# XTIO.net
KiCad netlist of a schematic drawn in Altium Designer
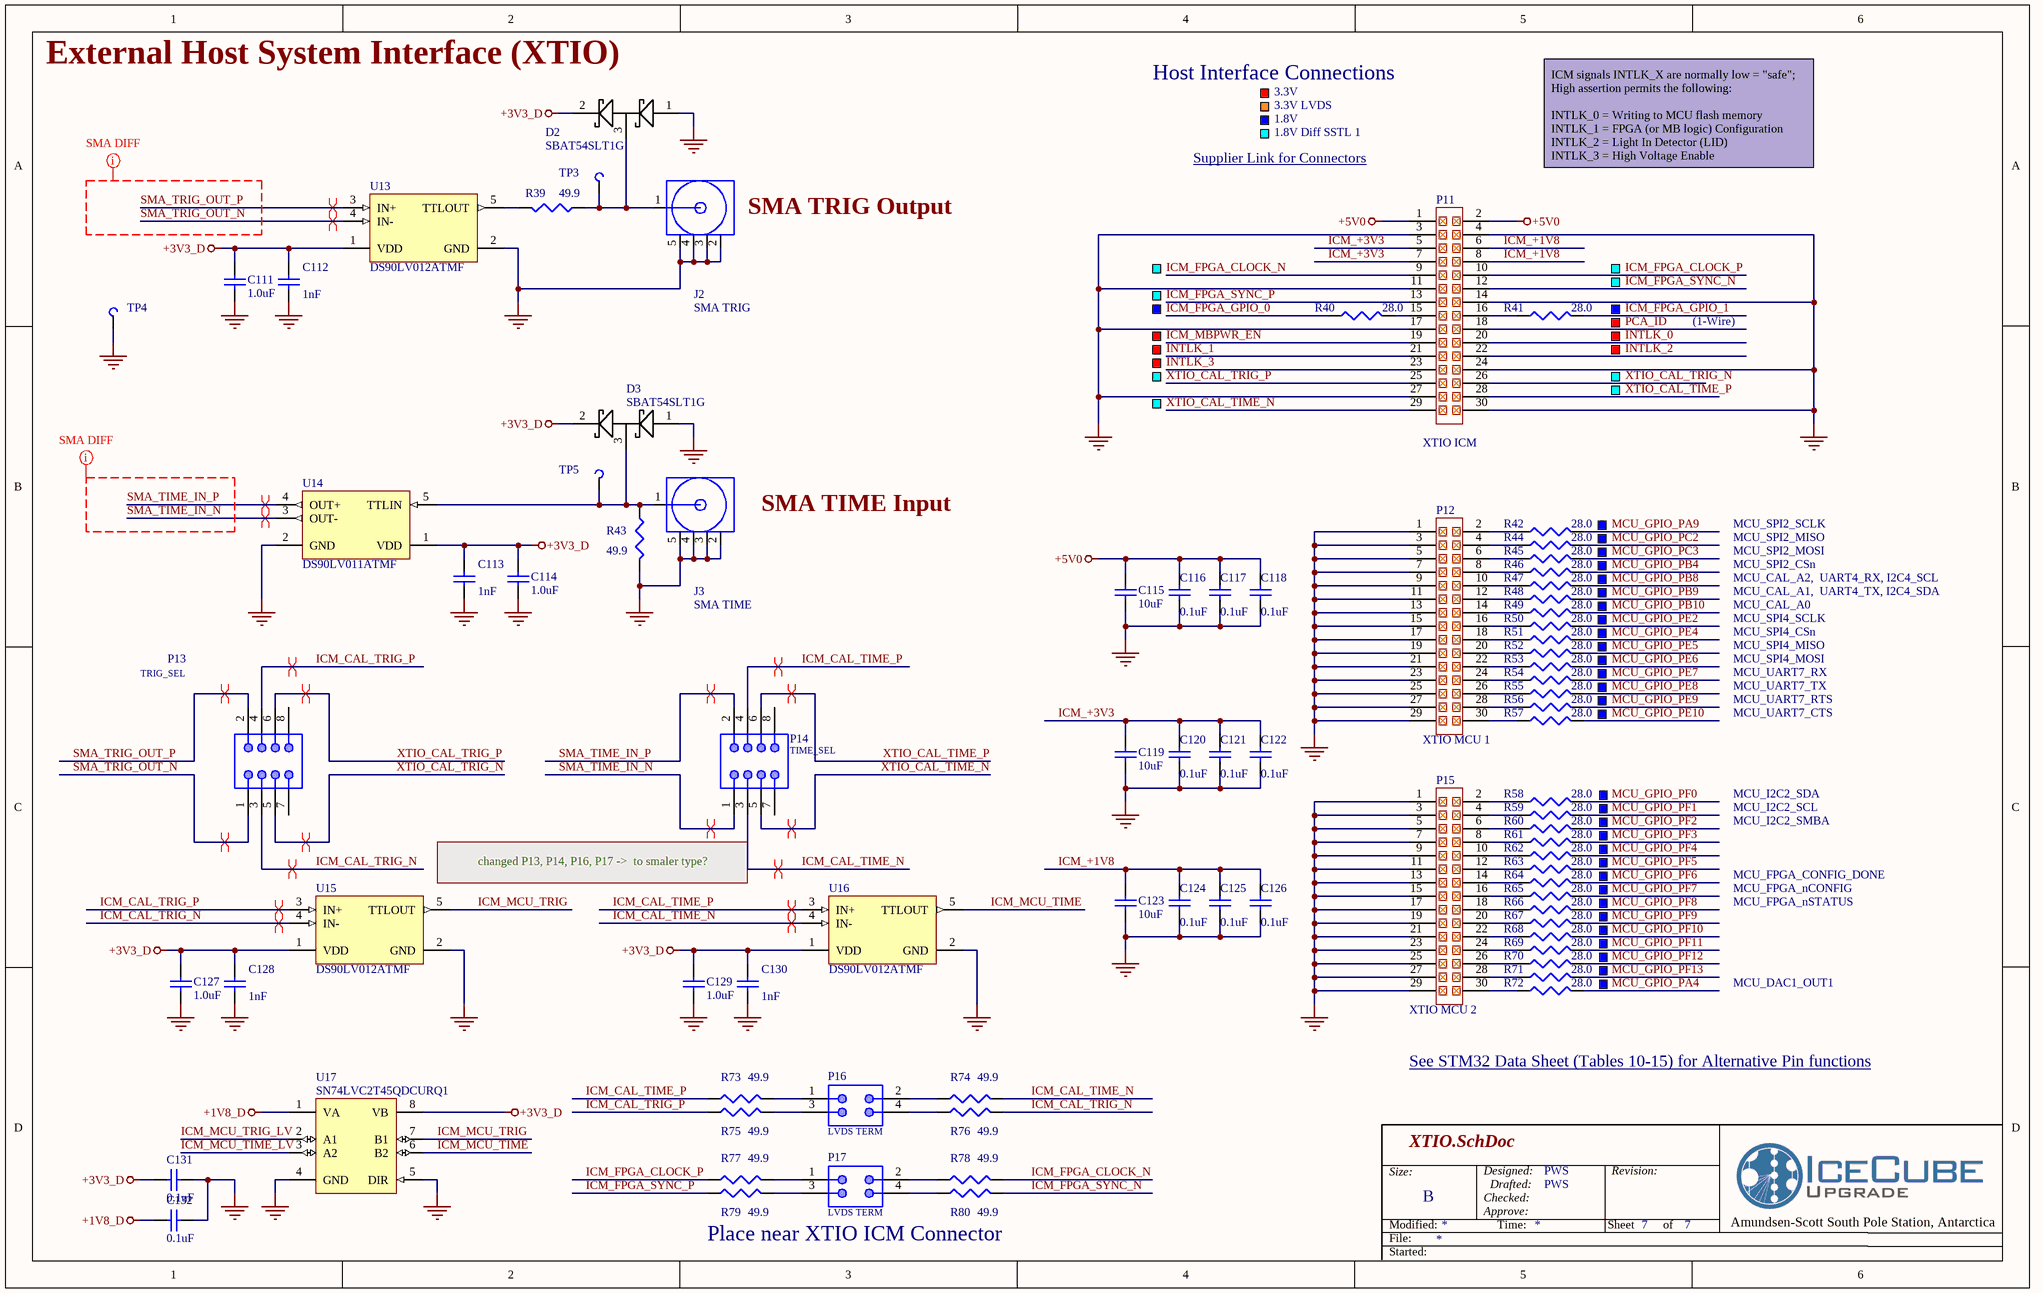
[diagram p0: XTIO.SchDoc]

(export (version "E")
  (design (tool "Eeschema 10.0.6"))
  (components
    (comp (ref "C111")
      (value "1.0uF_603_25V")
      (footprint "CAPC_0603")
      (description "1µF ±10% 25V Ceramic Capacitor X7R 0603 (1608 Metric)")
      (fields
        (field (name "MANUFACTURER") "Murata")
        (field (name "MANUFACTURER PART NUMBER") "GCJ188R71E105KA01D")
        (field (name "CAPACITANCE") "1.0uF")
      )
      (libsource (lib "Custom1") (part "CapC_1.0uF_603_25V"))
    )
    (comp (ref "C112")
      (value "1000pF_603_50V")
      (footprint "CAPC_0603")
      (description "Capacitor")
      (fields
        (field (name "MANUFACTURER") "Knowles Syfer")
        (field (name "MANUFACTURER PART NUMBER") "0603Y0500102KXT")
        (field (name "CAPACITANCE") "1nF")
      )
      (libsource (lib "Custom1") (part "CapC_1000pF_603_50V"))
    )
    (comp (ref "C113")
      (value "1000pF_603_50V")
      (footprint "CAPC_0603")
      (description "Capacitor")
      (fields
        (field (name "MANUFACTURER") "Knowles Syfer")
        (field (name "MANUFACTURER PART NUMBER") "0603Y0500102KXT")
        (field (name "CAPACITANCE") "1nF")
      )
      (libsource (lib "Custom1") (part "CapC_1000pF_603_50V"))
    )
    (comp (ref "C114")
      (value "1.0uF_603_25V")
      (footprint "CAPC_0603")
      (description "1µF ±10% 25V Ceramic Capacitor X7R 0603 (1608 Metric)")
      (fields
        (field (name "MANUFACTURER") "Murata")
        (field (name "MANUFACTURER PART NUMBER") "GCJ188R71E105KA01D")
        (field (name "CAPACITANCE") "1.0uF")
      )
      (libsource (lib "Custom1") (part "CapC_1.0uF_603_25V"))
    )
    (comp (ref "C115")
      (value "10uF_805_10V")
      (footprint "CAPC_0805")
      (description "Capacitor")
      (fields
        (field (name "MANUFACTURER") "Murata")
        (field (name "MANUFACTURER PART NUMBER") "GCJ21BR71A106KE01L")
        (field (name "CAPACITANCE") "10uF")
      )
      (libsource (lib "Custom1") (part "CapC_10uF_805_10V"))
    )
    (comp (ref "C116")
      (value "0.1uF_603_50V")
      (footprint "CAPC_0603")
      (description "0.1µF ±10% 50V Ceramic Capacitor X7R 0603 (1608 Metric)")
      (fields
        (field (name "MANUFACTURER") "Murata")
        (field (name "MANUFACTURER PART NUMBER") "GCJ188R71H104KA12D")
        (field (name "CAPACITANCE") "0.1uF")
      )
      (libsource (lib "Custom1") (part "CapC_0.1uF_603_50V_GCJ"))
    )
    (comp (ref "C117")
      (value "0.1uF_603_50V")
      (footprint "CAPC_0603")
      (description "0.1µF ±10% 50V Ceramic Capacitor X7R 0603 (1608 Metric)")
      (fields
        (field (name "MANUFACTURER") "Murata")
        (field (name "MANUFACTURER PART NUMBER") "GCJ188R71H104KA12D")
        (field (name "CAPACITANCE") "0.1uF")
      )
      (libsource (lib "Custom1") (part "CapC_0.1uF_603_50V_GCJ"))
    )
    (comp (ref "C118")
      (value "0.1uF_603_50V")
      (footprint "CAPC_0603")
      (description "0.1µF ±10% 50V Ceramic Capacitor X7R 0603 (1608 Metric)")
      (fields
        (field (name "MANUFACTURER") "Murata")
        (field (name "MANUFACTURER PART NUMBER") "GCJ188R71H104KA12D")
        (field (name "CAPACITANCE") "0.1uF")
      )
      (libsource (lib "Custom1") (part "CapC_0.1uF_603_50V_GCJ"))
    )
    (comp (ref "C119")
      (value "10uF_805_10V")
      (footprint "CAPC_0805")
      (description "Capacitor")
      (fields
        (field (name "MANUFACTURER") "Murata")
        (field (name "MANUFACTURER PART NUMBER") "GCJ21BR71A106KE01L")
        (field (name "CAPACITANCE") "10uF")
      )
      (libsource (lib "Custom1") (part "CapC_10uF_805_10V"))
    )
    (comp (ref "C120")
      (value "0.1uF_603_50V")
      (footprint "CAPC_0603")
      (description "0.1µF ±10% 50V Ceramic Capacitor X7R 0603 (1608 Metric)")
      (fields
        (field (name "MANUFACTURER") "Murata")
        (field (name "MANUFACTURER PART NUMBER") "GCJ188R71H104KA12D")
        (field (name "CAPACITANCE") "0.1uF")
      )
      (libsource (lib "Custom1") (part "CapC_0.1uF_603_50V_GCJ"))
    )
    (comp (ref "C121")
      (value "0.1uF_603_50V")
      (footprint "CAPC_0603")
      (description "0.1µF ±10% 50V Ceramic Capacitor X7R 0603 (1608 Metric)")
      (fields
        (field (name "MANUFACTURER") "Murata")
        (field (name "MANUFACTURER PART NUMBER") "GCJ188R71H104KA12D")
        (field (name "CAPACITANCE") "0.1uF")
      )
      (libsource (lib "Custom1") (part "CapC_0.1uF_603_50V_GCJ"))
    )
    (comp (ref "C122")
      (value "0.1uF_603_50V")
      (footprint "CAPC_0603")
      (description "0.1µF ±10% 50V Ceramic Capacitor X7R 0603 (1608 Metric)")
      (fields
        (field (name "MANUFACTURER") "Murata")
        (field (name "MANUFACTURER PART NUMBER") "GCJ188R71H104KA12D")
        (field (name "CAPACITANCE") "0.1uF")
      )
      (libsource (lib "Custom1") (part "CapC_0.1uF_603_50V_GCJ"))
    )
    (comp (ref "C123")
      (value "10uF_805_10V")
      (footprint "CAPC_0805")
      (description "Capacitor")
      (fields
        (field (name "MANUFACTURER") "Murata")
        (field (name "MANUFACTURER PART NUMBER") "GCJ21BR71A106KE01L")
        (field (name "CAPACITANCE") "10uF")
      )
      (libsource (lib "Custom1") (part "CapC_10uF_805_10V"))
    )
    (comp (ref "C124")
      (value "0.1uF_603_50V")
      (footprint "CAPC_0603")
      (description "0.1µF ±10% 50V Ceramic Capacitor X7R 0603 (1608 Metric)")
      (fields
        (field (name "MANUFACTURER") "Murata")
        (field (name "MANUFACTURER PART NUMBER") "GCJ188R71H104KA12D")
        (field (name "CAPACITANCE") "0.1uF")
      )
      (libsource (lib "Custom1") (part "CapC_0.1uF_603_50V_GCJ"))
    )
    (comp (ref "C125")
      (value "0.1uF_603_50V")
      (footprint "CAPC_0603")
      (description "0.1µF ±10% 50V Ceramic Capacitor X7R 0603 (1608 Metric)")
      (fields
        (field (name "MANUFACTURER") "Murata")
        (field (name "MANUFACTURER PART NUMBER") "GCJ188R71H104KA12D")
        (field (name "CAPACITANCE") "0.1uF")
      )
      (libsource (lib "Custom1") (part "CapC_0.1uF_603_50V_GCJ"))
    )
    (comp (ref "C126")
      (value "0.1uF_603_50V")
      (footprint "CAPC_0603")
      (description "0.1µF ±10% 50V Ceramic Capacitor X7R 0603 (1608 Metric)")
      (fields
        (field (name "MANUFACTURER") "Murata")
        (field (name "MANUFACTURER PART NUMBER") "GCJ188R71H104KA12D")
        (field (name "CAPACITANCE") "0.1uF")
      )
      (libsource (lib "Custom1") (part "CapC_0.1uF_603_50V_GCJ"))
    )
    (comp (ref "C127")
      (value "1.0uF_603_25V")
      (footprint "CAPC_0603")
      (description "1µF ±10% 25V Ceramic Capacitor X7R 0603 (1608 Metric)")
      (fields
        (field (name "MANUFACTURER") "Murata")
        (field (name "MANUFACTURER PART NUMBER") "GCJ188R71E105KA01D")
        (field (name "CAPACITANCE") "1.0uF")
      )
      (libsource (lib "Custom1") (part "CapC_1.0uF_603_25V"))
    )
    (comp (ref "C128")
      (value "1000pF_603_50V")
      (footprint "CAPC_0603")
      (description "Capacitor")
      (fields
        (field (name "MANUFACTURER") "Knowles Syfer")
        (field (name "MANUFACTURER PART NUMBER") "0603Y0500102KXT")
        (field (name "CAPACITANCE") "1nF")
      )
      (libsource (lib "Custom1") (part "CapC_1000pF_603_50V"))
    )
    (comp (ref "C129")
      (value "1.0uF_603_25V")
      (footprint "CAPC_0603")
      (description "1µF ±10% 25V Ceramic Capacitor X7R 0603 (1608 Metric)")
      (fields
        (field (name "MANUFACTURER") "Murata")
        (field (name "MANUFACTURER PART NUMBER") "GCJ188R71E105KA01D")
        (field (name "CAPACITANCE") "1.0uF")
      )
      (libsource (lib "Custom1") (part "CapC_1.0uF_603_25V"))
    )
    (comp (ref "C130")
      (value "1000pF_603_50V")
      (footprint "CAPC_0603")
      (description "Capacitor")
      (fields
        (field (name "MANUFACTURER") "Knowles Syfer")
        (field (name "MANUFACTURER PART NUMBER") "0603Y0500102KXT")
        (field (name "CAPACITANCE") "1nF")
      )
      (libsource (lib "Custom1") (part "CapC_1000pF_603_50V"))
    )
    (comp (ref "C131")
      (value "0.1uF_603_50V")
      (footprint "CAPC_0603")
      (description "0.1µF ±10% 50V Ceramic Capacitor X7R 0603 (1608 Metric)")
      (fields
        (field (name "MANUFACTURER") "TDK")
        (field (name "MANUFACTURER PART NUMBER") "CGJ3E2X7R1H104K080AA")
        (field (name "CAPACITANCE") "0.1uF")
      )
      (libsource (lib "Custom1") (part "CapC_0.1uF_603_50V"))
    )
    (comp (ref "C132")
      (value "0.1uF_603_50V")
      (footprint "CAPC_0603")
      (description "0.1µF ±10% 50V Ceramic Capacitor X7R 0603 (1608 Metric)")
      (fields
        (field (name "MANUFACTURER") "TDK")
        (field (name "MANUFACTURER PART NUMBER") "CGJ3E2X7R1H104K080AA")
        (field (name "CAPACITANCE") "0.1uF")
      )
      (libsource (lib "Custom1") (part "CapC_0.1uF_603_50V"))
    )
    (comp (ref "D2")
      (value "SBAT54SLT1G")
      (footprint "SOT-23")
      (description "DIODE ARRAY SCHOTTKY 30V SOT23-3")
      (fields (field (name "MANUFACTURER") "ON Semiconductor"))
      (libsource (lib "Custom1") (part "Diode ESD Pair"))
    )
    (comp (ref "D3")
      (value "SBAT54SLT1G")
      (footprint "SOT-23")
      (description "DIODE ARRAY SCHOTTKY 30V SOT23-3")
      (fields (field (name "MANUFACTURER") "ON Semiconductor"))
      (libsource (lib "Custom1") (part "Diode ESD Pair"))
    )
    (comp (ref "J2")
      (value "SMA TRIG")
      (footprint "SMA Vertical 200LS")
      (description "SMA Vertical, 0.200\"LS")
      (fields
        (field (name "MANUFACTURER") "Emerson Network Power Connectivity Johnson")
        (field (name "MANUFACTURER PART NUMBER") "142-0701-231")
      )
      (libsource (lib "Custom1") (part "SMA-Vertical"))
    )
    (comp (ref "J3")
      (value "SMA TIME")
      (footprint "SMA Vertical 200LS")
      (description "SMA Vertical, 0.200\"LS")
      (fields
        (field (name "MANUFACTURER") "Emerson Network Power Connectivity Johnson")
        (field (name "MANUFACTURER PART NUMBER") "142-0701-231")
      )
      (libsource (lib "Custom1") (part "SMA-Vertical"))
    )
    (comp (ref "P11")
      (value "XTIO ICM")
      (footprint "45230-220230")
      (description "CONN HEADER SMD 30POS 1.27MM")
      (fields (field (name "MANUFACTURER") "3M") (field (name "MANUFACTURER PART NUMBER") "45230-220230"))
      (libsource (lib "Custom1") (part "Header Male 3M-452 15x2"))
    )
    (comp (ref "P12")
      (value "XTIO MCU 1")
      (footprint "45230-220230")
      (description "CONN HEADER SMD 30POS 1.27MM")
      (fields (field (name "MANUFACTURER") "3M") (field (name "MANUFACTURER PART NUMBER") "45230-220230"))
      (libsource (lib "Custom1") (part "Header Male 3M-452 15x2"))
    )
    (comp (ref "P13")
      (value "TRIG_SEL")
      (footprint "62100821021")
      (description "WR-PHD Pin Header, SMT, pitch 1.27mm, Dual Row, Vertical, 8pin")
      (fields (field (name "PART NUMBER") "62100821021") (field (name "PUBLISHER") "Wurth Elektronik"))
      (libsource (lib "WR-PHD") (part "62100821021"))
    )
    (comp (ref "P14")
      (value "TIME_SEL")
      (footprint "62100821021")
      (description "WR-PHD Pin Header, SMT, pitch 1.27mm, Dual Row, Vertical, 8pin")
      (fields (field (name "PART NUMBER") "62100821021") (field (name "PUBLISHER") "Wurth Elektronik"))
      (libsource (lib "WR-PHD") (part "62100821021"))
    )
    (comp (ref "P15")
      (value "XTIO MCU 2")
      (footprint "45230-220230")
      (description "CONN HEADER SMD 30POS 1.27MM")
      (fields (field (name "MANUFACTURER") "3M") (field (name "MANUFACTURER PART NUMBER") "45230-220230"))
      (libsource (lib "Custom1") (part "Header Male 3M-452 15x2"))
    )
    (comp (ref "P16")
      (value "LVDS TERM")
      (footprint "62100421021")
      (description "WR-PHD Pin Header, SMT, pitch 1.27mm, Dual Row, Vertical, 4pin")
      (fields (field (name "PART NUMBER") "62100421021") (field (name "PUBLISHER") "Wurth Elektronik"))
      (libsource (lib "WR-PHD") (part "62100421021"))
    )
    (comp (ref "P17")
      (value "LVDS TERM")
      (footprint "62100421021")
      (description "WR-PHD Pin Header, SMT, pitch 1.27mm, Dual Row, Vertical, 4pin")
      (fields (field (name "PART NUMBER") "62100421021") (field (name "PUBLISHER") "Wurth Elektronik"))
      (libsource (lib "WR-PHD") (part "62100421021"))
    )
    (comp (ref "R39")
      (value "R_49.9_1206_1%")
      (footprint "RES_1206")
      (description "RES 50 OHM 1/2W 1% 1206 SMD")
      (fields
        (field (name "MANUFACTURER") "Panasonic")
        (field (name "MANUFACTURER PART NUMBER") "ERJ8ENF49R9V")
        (field (name "RESISTANCE") "49.9")
      )
      (libsource (lib "Custom1") (part "R_49.9_1206_1%"))
    )
    (comp (ref "R40")
      (value "R_28.0_603_1%")
      (footprint "RES_0603")
      (description "RES 28.0 OHM 1/10W 1% 0603 SMD")
      (fields
        (field (name "MANUFACTURER") "Panasonic")
        (field (name "MANUFACTURER PART NUMBER") "ERJ3EKF28R0V")
        (field (name "RESISTANCE") "28.0")
      )
      (libsource (lib "Custom1") (part "R_28.0_603_1%"))
    )
    (comp (ref "R41")
      (value "R_28.0_603_1%")
      (footprint "RES_0603")
      (description "RES 28.0 OHM 1/10W 1% 0603 SMD")
      (fields
        (field (name "MANUFACTURER") "Panasonic")
        (field (name "MANUFACTURER PART NUMBER") "ERJ3EKF28R0V")
        (field (name "RESISTANCE") "28.0")
      )
      (libsource (lib "Custom1") (part "R_28.0_603_1%"))
    )
    (comp (ref "R42")
      (value "R_28.0_603_1%")
      (footprint "RES_0603")
      (description "RES 28.0 OHM 1/10W 1% 0603 SMD")
      (fields
        (field (name "MANUFACTURER") "Panasonic")
        (field (name "MANUFACTURER PART NUMBER") "ERJ3EKF28R0V")
        (field (name "RESISTANCE") "28.0")
      )
      (libsource (lib "Custom1") (part "R_28.0_603_1%"))
    )
    (comp (ref "R43")
      (value "R_49.9_1206_1%")
      (footprint "RES_1206")
      (description "RES 50 OHM 1/2W 1% 1206 SMD")
      (fields
        (field (name "MANUFACTURER") "Panasonic")
        (field (name "MANUFACTURER PART NUMBER") "ERJ8ENF49R9V")
        (field (name "RESISTANCE") "49.9")
      )
      (libsource (lib "Custom1") (part "R_49.9_1206_1%"))
    )
    (comp (ref "R44")
      (value "R_28.0_603_1%")
      (footprint "RES_0603")
      (description "RES 28.0 OHM 1/10W 1% 0603 SMD")
      (fields
        (field (name "MANUFACTURER") "Panasonic")
        (field (name "MANUFACTURER PART NUMBER") "ERJ3EKF28R0V")
        (field (name "RESISTANCE") "28.0")
      )
      (libsource (lib "Custom1") (part "R_28.0_603_1%"))
    )
    (comp (ref "R45")
      (value "R_28.0_603_1%")
      (footprint "RES_0603")
      (description "RES 28.0 OHM 1/10W 1% 0603 SMD")
      (fields
        (field (name "MANUFACTURER") "Panasonic")
        (field (name "MANUFACTURER PART NUMBER") "ERJ3EKF28R0V")
        (field (name "RESISTANCE") "28.0")
      )
      (libsource (lib "Custom1") (part "R_28.0_603_1%"))
    )
    (comp (ref "R46")
      (value "R_28.0_603_1%")
      (footprint "RES_0603")
      (description "RES 28.0 OHM 1/10W 1% 0603 SMD")
      (fields
        (field (name "MANUFACTURER") "Panasonic")
        (field (name "MANUFACTURER PART NUMBER") "ERJ3EKF28R0V")
        (field (name "RESISTANCE") "28.0")
      )
      (libsource (lib "Custom1") (part "R_28.0_603_1%"))
    )
    (comp (ref "R47")
      (value "R_28.0_603_1%")
      (footprint "RES_0603")
      (description "RES 28.0 OHM 1/10W 1% 0603 SMD")
      (fields
        (field (name "MANUFACTURER") "Panasonic")
        (field (name "MANUFACTURER PART NUMBER") "ERJ3EKF28R0V")
        (field (name "RESISTANCE") "28.0")
      )
      (libsource (lib "Custom1") (part "R_28.0_603_1%"))
    )
    (comp (ref "R48")
      (value "R_28.0_603_1%")
      (footprint "RES_0603")
      (description "RES 28.0 OHM 1/10W 1% 0603 SMD")
      (fields
        (field (name "MANUFACTURER") "Panasonic")
        (field (name "MANUFACTURER PART NUMBER") "ERJ3EKF28R0V")
        (field (name "RESISTANCE") "28.0")
      )
      (libsource (lib "Custom1") (part "R_28.0_603_1%"))
    )
    (comp (ref "R49")
      (value "R_28.0_603_1%")
      (footprint "RES_0603")
      (description "RES 28.0 OHM 1/10W 1% 0603 SMD")
      (fields
        (field (name "MANUFACTURER") "Panasonic")
        (field (name "MANUFACTURER PART NUMBER") "ERJ3EKF28R0V")
        (field (name "RESISTANCE") "28.0")
      )
      (libsource (lib "Custom1") (part "R_28.0_603_1%"))
    )
    (comp (ref "R50")
      (value "R_28.0_603_1%")
      (footprint "RES_0603")
      (description "RES 28.0 OHM 1/10W 1% 0603 SMD")
      (fields
        (field (name "MANUFACTURER") "Panasonic")
        (field (name "MANUFACTURER PART NUMBER") "ERJ3EKF28R0V")
        (field (name "RESISTANCE") "28.0")
      )
      (libsource (lib "Custom1") (part "R_28.0_603_1%"))
    )
    (comp (ref "R51")
      (value "R_28.0_603_1%")
      (footprint "RES_0603")
      (description "RES 28.0 OHM 1/10W 1% 0603 SMD")
      (fields
        (field (name "MANUFACTURER") "Panasonic")
        (field (name "MANUFACTURER PART NUMBER") "ERJ3EKF28R0V")
        (field (name "RESISTANCE") "28.0")
      )
      (libsource (lib "Custom1") (part "R_28.0_603_1%"))
    )
    (comp (ref "R52")
      (value "R_28.0_603_1%")
      (footprint "RES_0603")
      (description "RES 28.0 OHM 1/10W 1% 0603 SMD")
      (fields
        (field (name "MANUFACTURER") "Panasonic")
        (field (name "MANUFACTURER PART NUMBER") "ERJ3EKF28R0V")
        (field (name "RESISTANCE") "28.0")
      )
      (libsource (lib "Custom1") (part "R_28.0_603_1%"))
    )
    (comp (ref "R53")
      (value "R_28.0_603_1%")
      (footprint "RES_0603")
      (description "RES 28.0 OHM 1/10W 1% 0603 SMD")
      (fields
        (field (name "MANUFACTURER") "Panasonic")
        (field (name "MANUFACTURER PART NUMBER") "ERJ3EKF28R0V")
        (field (name "RESISTANCE") "28.0")
      )
      (libsource (lib "Custom1") (part "R_28.0_603_1%"))
    )
    (comp (ref "R54")
      (value "R_28.0_603_1%")
      (footprint "RES_0603")
      (description "RES 28.0 OHM 1/10W 1% 0603 SMD")
      (fields
        (field (name "MANUFACTURER") "Panasonic")
        (field (name "MANUFACTURER PART NUMBER") "ERJ3EKF28R0V")
        (field (name "RESISTANCE") "28.0")
      )
      (libsource (lib "Custom1") (part "R_28.0_603_1%"))
    )
    (comp (ref "R55")
      (value "R_28.0_603_1%")
      (footprint "RES_0603")
      (description "RES 28.0 OHM 1/10W 1% 0603 SMD")
      (fields
        (field (name "MANUFACTURER") "Panasonic")
        (field (name "MANUFACTURER PART NUMBER") "ERJ3EKF28R0V")
        (field (name "RESISTANCE") "28.0")
      )
      (libsource (lib "Custom1") (part "R_28.0_603_1%"))
    )
    (comp (ref "R56")
      (value "R_28.0_603_1%")
      (footprint "RES_0603")
      (description "RES 28.0 OHM 1/10W 1% 0603 SMD")
      (fields
        (field (name "MANUFACTURER") "Panasonic")
        (field (name "MANUFACTURER PART NUMBER") "ERJ3EKF28R0V")
        (field (name "RESISTANCE") "28.0")
      )
      (libsource (lib "Custom1") (part "R_28.0_603_1%"))
    )
    (comp (ref "R57")
      (value "R_28.0_603_1%")
      (footprint "RES_0603")
      (description "RES 28.0 OHM 1/10W 1% 0603 SMD")
      (fields
        (field (name "MANUFACTURER") "Panasonic")
        (field (name "MANUFACTURER PART NUMBER") "ERJ3EKF28R0V")
        (field (name "RESISTANCE") "28.0")
      )
      (libsource (lib "Custom1") (part "R_28.0_603_1%"))
    )
    (comp (ref "R58")
      (value "R_28.0_603_1%")
      (footprint "RES_0603")
      (description "RES 28.0 OHM 1/10W 1% 0603 SMD")
      (fields
        (field (name "MANUFACTURER") "Panasonic")
        (field (name "MANUFACTURER PART NUMBER") "ERJ3EKF28R0V")
        (field (name "RESISTANCE") "28.0")
      )
      (libsource (lib "Custom1") (part "R_28.0_603_1%"))
    )
    (comp (ref "R59")
      (value "R_28.0_603_1%")
      (footprint "RES_0603")
      (description "RES 28.0 OHM 1/10W 1% 0603 SMD")
      (fields
        (field (name "MANUFACTURER") "Panasonic")
        (field (name "MANUFACTURER PART NUMBER") "ERJ3EKF28R0V")
        (field (name "RESISTANCE") "28.0")
      )
      (libsource (lib "Custom1") (part "R_28.0_603_1%"))
    )
    (comp (ref "R60")
      (value "R_28.0_603_1%")
      (footprint "RES_0603")
      (description "RES 28.0 OHM 1/10W 1% 0603 SMD")
      (fields
        (field (name "MANUFACTURER") "Panasonic")
        (field (name "MANUFACTURER PART NUMBER") "ERJ3EKF28R0V")
        (field (name "RESISTANCE") "28.0")
      )
      (libsource (lib "Custom1") (part "R_28.0_603_1%"))
    )
    (comp (ref "R61")
      (value "R_28.0_603_1%")
      (footprint "RES_0603")
      (description "RES 28.0 OHM 1/10W 1% 0603 SMD")
      (fields
        (field (name "MANUFACTURER") "Panasonic")
        (field (name "MANUFACTURER PART NUMBER") "ERJ3EKF28R0V")
        (field (name "RESISTANCE") "28.0")
      )
      (libsource (lib "Custom1") (part "R_28.0_603_1%"))
    )
    (comp (ref "R62")
      (value "R_28.0_603_1%")
      (footprint "RES_0603")
      (description "RES 28.0 OHM 1/10W 1% 0603 SMD")
      (fields
        (field (name "MANUFACTURER") "Panasonic")
        (field (name "MANUFACTURER PART NUMBER") "ERJ3EKF28R0V")
        (field (name "RESISTANCE") "28.0")
      )
      (libsource (lib "Custom1") (part "R_28.0_603_1%"))
    )
    (comp (ref "R63")
      (value "R_28.0_603_1%")
      (footprint "RES_0603")
      (description "RES 28.0 OHM 1/10W 1% 0603 SMD")
      (fields
        (field (name "MANUFACTURER") "Panasonic")
        (field (name "MANUFACTURER PART NUMBER") "ERJ3EKF28R0V")
        (field (name "RESISTANCE") "28.0")
      )
      (libsource (lib "Custom1") (part "R_28.0_603_1%"))
    )
    (comp (ref "R64")
      (value "R_28.0_603_1%")
      (footprint "RES_0603")
      (description "RES 28.0 OHM 1/10W 1% 0603 SMD")
      (fields
        (field (name "MANUFACTURER") "Panasonic")
        (field (name "MANUFACTURER PART NUMBER") "ERJ3EKF28R0V")
        (field (name "RESISTANCE") "28.0")
      )
      (libsource (lib "Custom1") (part "R_28.0_603_1%"))
    )
    (comp (ref "R65")
      (value "R_28.0_603_1%")
      (footprint "RES_0603")
      (description "RES 28.0 OHM 1/10W 1% 0603 SMD")
      (fields
        (field (name "MANUFACTURER") "Panasonic")
        (field (name "MANUFACTURER PART NUMBER") "ERJ3EKF28R0V")
        (field (name "RESISTANCE") "28.0")
      )
      (libsource (lib "Custom1") (part "R_28.0_603_1%"))
    )
    (comp (ref "R66")
      (value "R_28.0_603_1%")
      (footprint "RES_0603")
      (description "RES 28.0 OHM 1/10W 1% 0603 SMD")
      (fields
        (field (name "MANUFACTURER") "Panasonic")
        (field (name "MANUFACTURER PART NUMBER") "ERJ3EKF28R0V")
        (field (name "RESISTANCE") "28.0")
      )
      (libsource (lib "Custom1") (part "R_28.0_603_1%"))
    )
    (comp (ref "R67")
      (value "R_28.0_603_1%")
      (footprint "RES_0603")
      (description "RES 28.0 OHM 1/10W 1% 0603 SMD")
      (fields
        (field (name "MANUFACTURER") "Panasonic")
        (field (name "MANUFACTURER PART NUMBER") "ERJ3EKF28R0V")
        (field (name "RESISTANCE") "28.0")
      )
      (libsource (lib "Custom1") (part "R_28.0_603_1%"))
    )
    (comp (ref "R68")
      (value "R_28.0_603_1%")
      (footprint "RES_0603")
      (description "RES 28.0 OHM 1/10W 1% 0603 SMD")
      (fields
        (field (name "MANUFACTURER") "Panasonic")
        (field (name "MANUFACTURER PART NUMBER") "ERJ3EKF28R0V")
        (field (name "RESISTANCE") "28.0")
      )
      (libsource (lib "Custom1") (part "R_28.0_603_1%"))
    )
    (comp (ref "R69")
      (value "R_28.0_603_1%")
      (footprint "RES_0603")
      (description "RES 28.0 OHM 1/10W 1% 0603 SMD")
      (fields
        (field (name "MANUFACTURER") "Panasonic")
        (field (name "MANUFACTURER PART NUMBER") "ERJ3EKF28R0V")
        (field (name "RESISTANCE") "28.0")
      )
      (libsource (lib "Custom1") (part "R_28.0_603_1%"))
    )
    (comp (ref "R70")
      (value "R_28.0_603_1%")
      (footprint "RES_0603")
      (description "RES 28.0 OHM 1/10W 1% 0603 SMD")
      (fields
        (field (name "MANUFACTURER") "Panasonic")
        (field (name "MANUFACTURER PART NUMBER") "ERJ3EKF28R0V")
        (field (name "RESISTANCE") "28.0")
      )
      (libsource (lib "Custom1") (part "R_28.0_603_1%"))
    )
    (comp (ref "R71")
      (value "R_28.0_603_1%")
      (footprint "RES_0603")
      (description "RES 28.0 OHM 1/10W 1% 0603 SMD")
      (fields
        (field (name "MANUFACTURER") "Panasonic")
        (field (name "MANUFACTURER PART NUMBER") "ERJ3EKF28R0V")
        (field (name "RESISTANCE") "28.0")
      )
      (libsource (lib "Custom1") (part "R_28.0_603_1%"))
    )
    (comp (ref "R72")
      (value "R_28.0_603_1%")
      (footprint "RES_0603")
      (description "RES 28.0 OHM 1/10W 1% 0603 SMD")
      (fields
        (field (name "MANUFACTURER") "Panasonic")
        (field (name "MANUFACTURER PART NUMBER") "ERJ3EKF28R0V")
        (field (name "RESISTANCE") "28.0")
      )
      (libsource (lib "Custom1") (part "R_28.0_603_1%"))
    )
    (comp (ref "R73")
      (value "R_49.9_603_1%")
      (footprint "RES_0603")
      (description "RES 49.9 OHM 1/10W 1% 0603 SMD")
      (fields
        (field (name "MANUFACTURER") "Panasonic")
        (field (name "MANUFACTURER PART NUMBER") "ERJ3EKF49R9V")
        (field (name "RESISTANCE") "49.9")
      )
      (libsource (lib "Custom1") (part "R_49.9_603_1%"))
    )
    (comp (ref "R74")
      (value "R_49.9_603_1%")
      (footprint "RES_0603")
      (description "RES 49.9 OHM 1/10W 1% 0603 SMD")
      (fields
        (field (name "MANUFACTURER") "Panasonic")
        (field (name "MANUFACTURER PART NUMBER") "ERJ3EKF49R9V")
        (field (name "RESISTANCE") "49.9")
      )
      (libsource (lib "Custom1") (part "R_49.9_603_1%"))
    )
    (comp (ref "R75")
      (value "R_49.9_603_1%")
      (footprint "RES_0603")
      (description "RES 49.9 OHM 1/10W 1% 0603 SMD")
      (fields
        (field (name "MANUFACTURER") "Panasonic")
        (field (name "MANUFACTURER PART NUMBER") "ERJ3EKF49R9V")
        (field (name "RESISTANCE") "49.9")
      )
      (libsource (lib "Custom1") (part "R_49.9_603_1%"))
    )
    (comp (ref "R76")
      (value "R_49.9_603_1%")
      (footprint "RES_0603")
      (description "RES 49.9 OHM 1/10W 1% 0603 SMD")
      (fields
        (field (name "MANUFACTURER") "Panasonic")
        (field (name "MANUFACTURER PART NUMBER") "ERJ3EKF49R9V")
        (field (name "RESISTANCE") "49.9")
      )
      (libsource (lib "Custom1") (part "R_49.9_603_1%"))
    )
    (comp (ref "R77")
      (value "R_49.9_603_1%")
      (footprint "RES_0603")
      (description "RES 49.9 OHM 1/10W 1% 0603 SMD")
      (fields
        (field (name "MANUFACTURER") "Panasonic")
        (field (name "MANUFACTURER PART NUMBER") "ERJ3EKF49R9V")
        (field (name "RESISTANCE") "49.9")
      )
      (libsource (lib "Custom1") (part "R_49.9_603_1%"))
    )
    (comp (ref "R78")
      (value "R_49.9_603_1%")
      (footprint "RES_0603")
      (description "RES 49.9 OHM 1/10W 1% 0603 SMD")
      (fields
        (field (name "MANUFACTURER") "Panasonic")
        (field (name "MANUFACTURER PART NUMBER") "ERJ3EKF49R9V")
        (field (name "RESISTANCE") "49.9")
      )
      (libsource (lib "Custom1") (part "R_49.9_603_1%"))
    )
    (comp (ref "R79")
      (value "R_49.9_603_1%")
      (footprint "RES_0603")
      (description "RES 49.9 OHM 1/10W 1% 0603 SMD")
      (fields
        (field (name "MANUFACTURER") "Panasonic")
        (field (name "MANUFACTURER PART NUMBER") "ERJ3EKF49R9V")
        (field (name "RESISTANCE") "49.9")
      )
      (libsource (lib "Custom1") (part "R_49.9_603_1%"))
    )
    (comp (ref "R80")
      (value "R_49.9_603_1%")
      (footprint "RES_0603")
      (description "RES 49.9 OHM 1/10W 1% 0603 SMD")
      (fields
        (field (name "MANUFACTURER") "Panasonic")
        (field (name "MANUFACTURER PART NUMBER") "ERJ3EKF49R9V")
        (field (name "RESISTANCE") "49.9")
      )
      (libsource (lib "Custom1") (part "R_49.9_603_1%"))
    )
    (comp (ref "TP3")
      (value "PC TEST POINT MINI SMD")
      (footprint "Test Point SM")
      (description "5019KCT-ND")
      (fields
        (field (name "MANUFACTURER") "Keystone Electronics")
        (field (name "MANUFACTURER PART NUMBER") "5019")
      )
      (libsource (lib "Custom1") (part "Test Point SM"))
    )
    (comp (ref "TP4")
      (value "PC TEST POINT MINI SMD")
      (footprint "Test Point SM")
      (description "5019KCT-ND")
      (fields
        (field (name "MANUFACTURER") "Keystone Electronics")
        (field (name "MANUFACTURER PART NUMBER") "5019")
      )
      (libsource (lib "Custom1") (part "Test Point SM"))
    )
    (comp (ref "TP5")
      (value "PC TEST POINT MINI SMD")
      (footprint "Test Point SM")
      (description "5019KCT-ND")
      (fields
        (field (name "MANUFACTURER") "Keystone Electronics")
        (field (name "MANUFACTURER PART NUMBER") "5019")
      )
      (libsource (lib "") (part "Test Point SM_1"))
    )
    (comp (ref "U13")
      (value "DS90LV012ATMF")
      (footprint "MF05A_N")
      (description "3V LVDS Single CMOS Differential Line Receiver, 5-pin SOT-23")
      (fields
        (field (name "MANUFACTURER") "TI National Semiconductor")
        (field (name "MANUFACTURER PART NUMBER") "DS90LV012ATMF/NOPB")
      )
      (libsource (lib "Custom1") (part "DS90LV012ATMF"))
    )
    (comp (ref "U14")
      (value "DS90LV011ATMF")
      (footprint "MF05A_N")
      (description "Single High Speed Differential Driver, 5-pin SOT-23")
      (fields
        (field (name "MANUFACTURER") "Texas Instruments")
        (field (name "MANUFACTURER PART NUMBER") "DS90LV011ATMF/NOPB")
      )
      (libsource (lib "Custom1") (part "DS90LV011ATMF"))
    )
    (comp (ref "U15")
      (value "DS90LV012ATMF")
      (footprint "MF05A_N")
      (description "3V LVDS Single CMOS Differential Line Receiver, 5-pin SOT-23")
      (fields
        (field (name "MANUFACTURER") "TI National Semiconductor")
        (field (name "MANUFACTURER PART NUMBER") "DS90LV012ATMF/NOPB")
      )
      (libsource (lib "Custom1") (part "DS90LV012ATMF"))
    )
    (comp (ref "U16")
      (value "DS90LV012ATMF")
      (footprint "MF05A_N")
      (description "3V LVDS Single CMOS Differential Line Receiver, 5-pin SOT-23")
      (fields
        (field (name "MANUFACTURER") "TI National Semiconductor")
        (field (name "MANUFACTURER PART NUMBER") "DS90LV012ATMF/NOPB")
      )
      (libsource (lib "Custom1") (part "DS90LV012ATMF"))
    )
    (comp (ref "U17")
      (value "SN74LVC2T45QDCURQ1")
      (footprint "TI-DGK8_N")
      (description "Voltage Level Translator Bidirectional 1 Circuit 2 Channel 420Mbps SM8 (SSOP)")
      (fields
        (field (name "GENERIC PART NUMBER") "SN74LVC2T45-Q1")
        (field (name "MANUFACTURER") "Texas Instruments")
      )
      (libsource (lib "Custom1") (part "SN74LVC2T45QDCURQ1"))
    )
  )
  (nets
    (net (code "1") (name "+1V8_D") (class "Default")
      (node (ref "C132") (pin "2") (pinfunction "2_2") (pintype "passive"))
      (node (ref "U17") (pin "1") (pinfunction "VA_1") (pintype "power_in"))
    )
    (net (code "2") (name "+3V3_D") (class "Default")
      (node (ref "C111") (pin "2") (pinfunction "2_2") (pintype "passive"))
      (node (ref "C112") (pin "2") (pinfunction "2_2") (pintype "passive"))
      (node (ref "C113") (pin "2") (pinfunction "2_2") (pintype "passive"))
      (node (ref "C114") (pin "2") (pinfunction "2_2") (pintype "passive"))
      (node (ref "C127") (pin "2") (pinfunction "2_2") (pintype "passive"))
      (node (ref "C128") (pin "2") (pinfunction "2_2") (pintype "passive"))
      (node (ref "C129") (pin "2") (pinfunction "2_2") (pintype "passive"))
      (node (ref "C130") (pin "2") (pinfunction "2_2") (pintype "passive"))
      (node (ref "C131") (pin "2") (pinfunction "2_2") (pintype "passive"))
      (node (ref "D2") (pin "2") (pinfunction "2_2") (pintype "passive"))
      (node (ref "D3") (pin "2") (pinfunction "2_2") (pintype "passive"))
      (node (ref "U13") (pin "1") (pinfunction "VDD_1") (pintype "power_in"))
      (node (ref "U14") (pin "1") (pinfunction "VDD_1") (pintype "power_in"))
      (node (ref "U15") (pin "1") (pinfunction "VDD_1") (pintype "power_in"))
      (node (ref "U16") (pin "1") (pinfunction "VDD_1") (pintype "power_in"))
      (node (ref "U17") (pin "8") (pinfunction "VB_8") (pintype "power_in"))
    )
    (net (code "3") (name "+5V0") (class "Default")
      (node (ref "C115") (pin "2") (pinfunction "2_2") (pintype "passive"))
      (node (ref "C116") (pin "2") (pinfunction "2_2") (pintype "passive"))
      (node (ref "C117") (pin "2") (pinfunction "2_2") (pintype "passive"))
      (node (ref "C118") (pin "2") (pinfunction "2_2") (pintype "passive"))
      (node (ref "P11") (pin "1") (pinfunction "1_1") (pintype "passive"))
      (node (ref "P11") (pin "2") (pinfunction "2_2") (pintype "passive"))
    )
    (net (code "4") (name "/ICM_+1V8") (class "Default")
      (node (ref "C123") (pin "2") (pinfunction "2_2") (pintype "passive"))
      (node (ref "C124") (pin "2") (pinfunction "2_2") (pintype "passive"))
      (node (ref "C125") (pin "2") (pinfunction "2_2") (pintype "passive"))
      (node (ref "C126") (pin "2") (pinfunction "2_2") (pintype "passive"))
      (node (ref "P11") (pin "6") (pinfunction "6_6") (pintype "passive"))
      (node (ref "P11") (pin "8") (pinfunction "8_8") (pintype "passive"))
    )
    (net (code "5") (name "/ICM_+3V3") (class "Default")
      (node (ref "C119") (pin "2") (pinfunction "2_2") (pintype "passive"))
      (node (ref "C120") (pin "2") (pinfunction "2_2") (pintype "passive"))
      (node (ref "C121") (pin "2") (pinfunction "2_2") (pintype "passive"))
      (node (ref "C122") (pin "2") (pinfunction "2_2") (pintype "passive"))
      (node (ref "P11") (pin "5") (pinfunction "5_5") (pintype "passive"))
      (node (ref "P11") (pin "7") (pinfunction "7_7") (pintype "passive"))
    )
    (net (code "6") (name "/ICM_CAL_TIME_N") (class "Default")
      (node (ref "P14") (pin "3") (pinfunction "3_3") (pintype "passive"))
      (node (ref "R74") (pin "2") (pinfunction "2_2") (pintype "passive"))
      (node (ref "U16") (pin "4") (pinfunction "IN-_4") (pintype "input"))
    )
    (net (code "7") (name "/ICM_CAL_TIME_P") (class "Default")
      (node (ref "P14") (pin "4") (pinfunction "4_4") (pintype "passive"))
      (node (ref "R73") (pin "1") (pinfunction "1_1") (pintype "passive"))
      (node (ref "U16") (pin "3") (pinfunction "IN+_3") (pintype "input"))
    )
    (net (code "8") (name "/ICM_CAL_TRIG_N") (class "Default")
      (node (ref "P13") (pin "3") (pinfunction "3_3") (pintype "passive"))
      (node (ref "R76") (pin "2") (pinfunction "2_2") (pintype "passive"))
      (node (ref "U15") (pin "4") (pinfunction "IN-_4") (pintype "input"))
    )
    (net (code "9") (name "/ICM_CAL_TRIG_P") (class "Default")
      (node (ref "P13") (pin "4") (pinfunction "4_4") (pintype "passive"))
      (node (ref "R75") (pin "1") (pinfunction "1_1") (pintype "passive"))
      (node (ref "U15") (pin "3") (pinfunction "IN+_3") (pintype "input"))
    )
    (net (code "10") (name "/ICM_FPGA_CLOCK_N") (class "Default")
      (node (ref "P11") (pin "9") (pinfunction "9_9") (pintype "passive"))
      (node (ref "R78") (pin "2") (pinfunction "2_2") (pintype "passive"))
    )
    (net (code "11") (name "/ICM_FPGA_CLOCK_P") (class "Default")
      (node (ref "P11") (pin "10") (pinfunction "10_10") (pintype "passive"))
      (node (ref "R77") (pin "1") (pinfunction "1_1") (pintype "passive"))
    )
    (net (code "12") (name "/ICM_FPGA_GPIO_0") (class "Default")
      (node (ref "R40") (pin "1") (pinfunction "1_1") (pintype "passive"))
    )
    (net (code "13") (name "/ICM_FPGA_GPIO_1") (class "Default")
      (node (ref "R41") (pin "2") (pinfunction "2_2") (pintype "passive"))
    )
    (net (code "14") (name "/ICM_FPGA_SYNC_N") (class "Default")
      (node (ref "P11") (pin "12") (pinfunction "12_12") (pintype "passive"))
      (node (ref "R80") (pin "2") (pinfunction "2_2") (pintype "passive"))
    )
    (net (code "15") (name "/ICM_FPGA_SYNC_P") (class "Default")
      (node (ref "P11") (pin "13") (pinfunction "13_13") (pintype "passive"))
      (node (ref "R79") (pin "1") (pinfunction "1_1") (pintype "passive"))
    )
    (net (code "16") (name "/ICM_MBPWR_EN") (class "Default")
      (node (ref "P11") (pin "19") (pinfunction "19_19") (pintype "passive"))
    )
    (net (code "17") (name "/ICM_MCU_TIME") (class "Default")
      (node (ref "U16") (pin "5") (pinfunction "TTLOUT_5") (pintype "output"))
      (node (ref "U17") (pin "6") (pinfunction "B2_6") (pintype "bidirectional"))
    )
    (net (code "18") (name "/ICM_MCU_TIME_LV") (class "Default")
      (node (ref "U17") (pin "3") (pinfunction "A2_3") (pintype "bidirectional"))
    )
    (net (code "19") (name "/ICM_MCU_TRIG") (class "Default")
      (node (ref "U15") (pin "5") (pinfunction "TTLOUT_5") (pintype "output"))
      (node (ref "U17") (pin "7") (pinfunction "B1_7") (pintype "bidirectional"))
    )
    (net (code "20") (name "/ICM_MCU_TRIG_LV") (class "Default")
      (node (ref "U17") (pin "2") (pinfunction "A1_2") (pintype "bidirectional"))
    )
    (net (code "21") (name "/INTLK_0") (class "Default")
      (node (ref "P11") (pin "20") (pinfunction "20_20") (pintype "passive"))
    )
    (net (code "22") (name "/INTLK_1") (class "Default")
      (node (ref "P11") (pin "21") (pinfunction "21_21") (pintype "passive"))
    )
    (net (code "23") (name "/INTLK_2") (class "Default")
      (node (ref "P11") (pin "22") (pinfunction "22_22") (pintype "passive"))
    )
    (net (code "24") (name "/INTLK_3") (class "Default")
      (node (ref "P11") (pin "23") (pinfunction "23_23") (pintype "passive"))
    )
    (net (code "25") (name "/MCU_GPIO_PA4") (class "Default")
      (node (ref "R72") (pin "2") (pinfunction "2_2") (pintype "passive"))
    )
    (net (code "26") (name "/MCU_GPIO_PA9") (class "Default")
      (node (ref "R42") (pin "2") (pinfunction "2_2") (pintype "passive"))
    )
    (net (code "27") (name "/MCU_GPIO_PB4") (class "Default")
      (node (ref "R46") (pin "2") (pinfunction "2_2") (pintype "passive"))
    )
    (net (code "28") (name "/MCU_GPIO_PB8") (class "Default")
      (node (ref "R47") (pin "2") (pinfunction "2_2") (pintype "passive"))
    )
    (net (code "29") (name "/MCU_GPIO_PB9") (class "Default")
      (node (ref "R48") (pin "2") (pinfunction "2_2") (pintype "passive"))
    )
    (net (code "30") (name "/MCU_GPIO_PB10") (class "Default")
      (node (ref "R49") (pin "2") (pinfunction "2_2") (pintype "passive"))
    )
    (net (code "31") (name "/MCU_GPIO_PC2") (class "Default")
      (node (ref "R44") (pin "2") (pinfunction "2_2") (pintype "passive"))
    )
    (net (code "32") (name "/MCU_GPIO_PC3") (class "Default")
      (node (ref "R45") (pin "2") (pinfunction "2_2") (pintype "passive"))
    )
    (net (code "33") (name "/MCU_GPIO_PE2") (class "Default")
      (node (ref "R50") (pin "2") (pinfunction "2_2") (pintype "passive"))
    )
    (net (code "34") (name "/MCU_GPIO_PE4") (class "Default")
      (node (ref "R51") (pin "2") (pinfunction "2_2") (pintype "passive"))
    )
    (net (code "35") (name "/MCU_GPIO_PE5") (class "Default")
      (node (ref "R52") (pin "2") (pinfunction "2_2") (pintype "passive"))
    )
    (net (code "36") (name "/MCU_GPIO_PE6") (class "Default")
      (node (ref "R53") (pin "2") (pinfunction "2_2") (pintype "passive"))
    )
    (net (code "37") (name "/MCU_GPIO_PE7") (class "Default")
      (node (ref "R54") (pin "2") (pinfunction "2_2") (pintype "passive"))
    )
    (net (code "38") (name "/MCU_GPIO_PE8") (class "Default")
      (node (ref "R55") (pin "2") (pinfunction "2_2") (pintype "passive"))
    )
    (net (code "39") (name "/MCU_GPIO_PE9") (class "Default")
      (node (ref "R56") (pin "2") (pinfunction "2_2") (pintype "passive"))
    )
    (net (code "40") (name "/MCU_GPIO_PE10") (class "Default")
      (node (ref "R57") (pin "2") (pinfunction "2_2") (pintype "passive"))
    )
    (net (code "41") (name "/MCU_GPIO_PF0") (class "Default")
      (node (ref "R58") (pin "2") (pinfunction "2_2") (pintype "passive"))
    )
    (net (code "42") (name "/MCU_GPIO_PF1") (class "Default")
      (node (ref "R59") (pin "2") (pinfunction "2_2") (pintype "passive"))
    )
    (net (code "43") (name "/MCU_GPIO_PF2") (class "Default")
      (node (ref "R60") (pin "2") (pinfunction "2_2") (pintype "passive"))
    )
    (net (code "44") (name "/MCU_GPIO_PF3") (class "Default")
      (node (ref "R61") (pin "2") (pinfunction "2_2") (pintype "passive"))
    )
    (net (code "45") (name "/MCU_GPIO_PF4") (class "Default")
      (node (ref "R62") (pin "2") (pinfunction "2_2") (pintype "passive"))
    )
    (net (code "46") (name "/MCU_GPIO_PF5") (class "Default")
      (node (ref "R63") (pin "2") (pinfunction "2_2") (pintype "passive"))
    )
    (net (code "47") (name "/MCU_GPIO_PF6") (class "Default")
      (node (ref "R64") (pin "2") (pinfunction "2_2") (pintype "passive"))
    )
    (net (code "48") (name "/MCU_GPIO_PF7") (class "Default")
      (node (ref "R65") (pin "2") (pinfunction "2_2") (pintype "passive"))
    )
    (net (code "49") (name "/MCU_GPIO_PF8") (class "Default")
      (node (ref "R66") (pin "2") (pinfunction "2_2") (pintype "passive"))
    )
    (net (code "50") (name "/MCU_GPIO_PF9") (class "Default")
      (node (ref "R67") (pin "2") (pinfunction "2_2") (pintype "passive"))
    )
    (net (code "51") (name "/MCU_GPIO_PF10") (class "Default")
      (node (ref "R68") (pin "2") (pinfunction "2_2") (pintype "passive"))
    )
    (net (code "52") (name "/MCU_GPIO_PF11") (class "Default")
      (node (ref "R69") (pin "2") (pinfunction "2_2") (pintype "passive"))
    )
    (net (code "53") (name "/MCU_GPIO_PF12") (class "Default")
      (node (ref "R70") (pin "2") (pinfunction "2_2") (pintype "passive"))
    )
    (net (code "54") (name "/MCU_GPIO_PF13") (class "Default")
      (node (ref "R71") (pin "2") (pinfunction "2_2") (pintype "passive"))
    )
    (net (code "55") (name "/PCA_ID") (class "Default")
      (node (ref "P11") (pin "18") (pinfunction "18_18") (pintype "passive"))
    )
    (net (code "56") (name "/SMA_TIME_IN_N") (class "Default")
      (node (ref "P14") (pin "1") (pinfunction "1_1") (pintype "passive"))
      (node (ref "U14") (pin "3") (pinfunction "OUT-_3") (pintype "output"))
    )
    (net (code "57") (name "/SMA_TIME_IN_P") (class "Default")
      (node (ref "P14") (pin "2") (pinfunction "2_2") (pintype "passive"))
      (node (ref "U14") (pin "4") (pinfunction "OUT+_4") (pintype "output"))
    )
    (net (code "58") (name "/SMA_TRIG_OUT_N") (class "Default")
      (node (ref "P13") (pin "1") (pinfunction "1_1") (pintype "passive"))
      (node (ref "U13") (pin "4") (pinfunction "IN-_4") (pintype "input"))
    )
    (net (code "59") (name "/SMA_TRIG_OUT_P") (class "Default")
      (node (ref "P13") (pin "2") (pinfunction "2_2") (pintype "passive"))
      (node (ref "U13") (pin "3") (pinfunction "IN+_3") (pintype "input"))
    )
    (net (code "60") (name "/XTIO_CAL_TIME_N") (class "Default")
      (node (ref "P11") (pin "29") (pinfunction "29_29") (pintype "passive"))
      (node (ref "P14") (pin "5") (pinfunction "5_5") (pintype "passive"))
    )
    (net (code "61") (name "/XTIO_CAL_TIME_P") (class "Default")
      (node (ref "P11") (pin "28") (pinfunction "28_28") (pintype "passive"))
      (node (ref "P14") (pin "6") (pinfunction "6_6") (pintype "passive"))
    )
    (net (code "62") (name "/XTIO_CAL_TRIG_N") (class "Default")
      (node (ref "P11") (pin "26") (pinfunction "26_26") (pintype "passive"))
      (node (ref "P13") (pin "5") (pinfunction "5_5") (pintype "passive"))
    )
    (net (code "63") (name "/XTIO_CAL_TRIG_P") (class "Default")
      (node (ref "P11") (pin "25") (pinfunction "25_25") (pintype "passive"))
      (node (ref "P13") (pin "6") (pinfunction "6_6") (pintype "passive"))
    )
    (net (code "64") (name "GND") (class "Default")
      (node (ref "C111") (pin "1") (pinfunction "1_1") (pintype "passive"))
      (node (ref "C112") (pin "1") (pinfunction "1_1") (pintype "passive"))
      (node (ref "C113") (pin "1") (pinfunction "1_1") (pintype "passive"))
      (node (ref "C114") (pin "1") (pinfunction "1_1") (pintype "passive"))
      (node (ref "C115") (pin "1") (pinfunction "1_1") (pintype "passive"))
      (node (ref "C116") (pin "1") (pinfunction "1_1") (pintype "passive"))
      (node (ref "C117") (pin "1") (pinfunction "1_1") (pintype "passive"))
      (node (ref "C118") (pin "1") (pinfunction "1_1") (pintype "passive"))
      (node (ref "C119") (pin "1") (pinfunction "1_1") (pintype "passive"))
      (node (ref "C120") (pin "1") (pinfunction "1_1") (pintype "passive"))
      (node (ref "C121") (pin "1") (pinfunction "1_1") (pintype "passive"))
      (node (ref "C122") (pin "1") (pinfunction "1_1") (pintype "passive"))
      (node (ref "C123") (pin "1") (pinfunction "1_1") (pintype "passive"))
      (node (ref "C124") (pin "1") (pinfunction "1_1") (pintype "passive"))
      (node (ref "C125") (pin "1") (pinfunction "1_1") (pintype "passive"))
      (node (ref "C126") (pin "1") (pinfunction "1_1") (pintype "passive"))
      (node (ref "C127") (pin "1") (pinfunction "1_1") (pintype "passive"))
      (node (ref "C128") (pin "1") (pinfunction "1_1") (pintype "passive"))
      (node (ref "C129") (pin "1") (pinfunction "1_1") (pintype "passive"))
      (node (ref "C130") (pin "1") (pinfunction "1_1") (pintype "passive"))
      (node (ref "C131") (pin "1") (pinfunction "1_1") (pintype "passive"))
      (node (ref "C132") (pin "1") (pinfunction "1_1") (pintype "passive"))
      (node (ref "D2") (pin "1") (pinfunction "1_1") (pintype "passive"))
      (node (ref "D3") (pin "1") (pinfunction "1_1") (pintype "passive"))
      (node (ref "J2") (pin "2") (pinfunction "GND_2") (pintype "power_in"))
      (node (ref "J2") (pin "3") (pinfunction "GND_3") (pintype "power_in"))
      (node (ref "J2") (pin "4") (pinfunction "GND_4") (pintype "power_in"))
      (node (ref "J2") (pin "5") (pinfunction "GND_5") (pintype "power_in"))
      (node (ref "J3") (pin "2") (pinfunction "GND_2") (pintype "power_in"))
      (node (ref "J3") (pin "3") (pinfunction "GND_3") (pintype "power_in"))
      (node (ref "J3") (pin "4") (pinfunction "GND_4") (pintype "power_in"))
      (node (ref "J3") (pin "5") (pinfunction "GND_5") (pintype "power_in"))
      (node (ref "P11") (pin "11") (pinfunction "11_11") (pintype "passive"))
      (node (ref "P11") (pin "14") (pinfunction "14_14") (pintype "passive"))
      (node (ref "P11") (pin "17") (pinfunction "17_17") (pintype "passive"))
      (node (ref "P11") (pin "24") (pinfunction "24_24") (pintype "passive"))
      (node (ref "P11") (pin "27") (pinfunction "27_27") (pintype "passive"))
      (node (ref "P11") (pin "3") (pinfunction "3_3") (pintype "passive"))
      (node (ref "P11") (pin "30") (pinfunction "30_30") (pintype "passive"))
      (node (ref "P11") (pin "4") (pinfunction "4_4") (pintype "passive"))
      (node (ref "P12") (pin "1") (pinfunction "1_1") (pintype "passive"))
      (node (ref "P12") (pin "11") (pinfunction "11_11") (pintype "passive"))
      (node (ref "P12") (pin "13") (pinfunction "13_13") (pintype "passive"))
      (node (ref "P12") (pin "15") (pinfunction "15_15") (pintype "passive"))
      (node (ref "P12") (pin "17") (pinfunction "17_17") (pintype "passive"))
      (node (ref "P12") (pin "19") (pinfunction "19_19") (pintype "passive"))
      (node (ref "P12") (pin "21") (pinfunction "21_21") (pintype "passive"))
      (node (ref "P12") (pin "23") (pinfunction "23_23") (pintype "passive"))
      (node (ref "P12") (pin "25") (pinfunction "25_25") (pintype "passive"))
      (node (ref "P12") (pin "27") (pinfunction "27_27") (pintype "passive"))
      (node (ref "P12") (pin "29") (pinfunction "29_29") (pintype "passive"))
      (node (ref "P12") (pin "3") (pinfunction "3_3") (pintype "passive"))
      (node (ref "P12") (pin "5") (pinfunction "5_5") (pintype "passive"))
      (node (ref "P12") (pin "7") (pinfunction "7_7") (pintype "passive"))
      (node (ref "P12") (pin "9") (pinfunction "9_9") (pintype "passive"))
      (node (ref "P15") (pin "1") (pinfunction "1_1") (pintype "passive"))
      (node (ref "P15") (pin "11") (pinfunction "11_11") (pintype "passive"))
      (node (ref "P15") (pin "13") (pinfunction "13_13") (pintype "passive"))
      (node (ref "P15") (pin "15") (pinfunction "15_15") (pintype "passive"))
      (node (ref "P15") (pin "17") (pinfunction "17_17") (pintype "passive"))
      (node (ref "P15") (pin "19") (pinfunction "19_19") (pintype "passive"))
      (node (ref "P15") (pin "21") (pinfunction "21_21") (pintype "passive"))
      (node (ref "P15") (pin "23") (pinfunction "23_23") (pintype "passive"))
      (node (ref "P15") (pin "25") (pinfunction "25_25") (pintype "passive"))
      (node (ref "P15") (pin "27") (pinfunction "27_27") (pintype "passive"))
      (node (ref "P15") (pin "29") (pinfunction "29_29") (pintype "passive"))
      (node (ref "P15") (pin "3") (pinfunction "3_3") (pintype "passive"))
      (node (ref "P15") (pin "5") (pinfunction "5_5") (pintype "passive"))
      (node (ref "P15") (pin "7") (pinfunction "7_7") (pintype "passive"))
      (node (ref "P15") (pin "9") (pinfunction "9_9") (pintype "passive"))
      (node (ref "R43") (pin "1") (pinfunction "1_1") (pintype "passive"))
      (node (ref "TP4") (pin "1") (pinfunction "1_1") (pintype "passive"))
      (node (ref "U13") (pin "2") (pinfunction "GND_2") (pintype "power_in"))
      (node (ref "U14") (pin "2") (pinfunction "GND_2") (pintype "power_in"))
      (node (ref "U15") (pin "2") (pinfunction "GND_2") (pintype "power_in"))
      (node (ref "U16") (pin "2") (pinfunction "GND_2") (pintype "power_in"))
      (node (ref "U17") (pin "4") (pinfunction "GND_4") (pintype "power_in"))
      (node (ref "U17") (pin "5") (pinfunction "DIR_5") (pintype "input"))
    )
    (net (code "65") (name "Net-(J2-Signal)") (class "Default")
      (node (ref "D2") (pin "3") (pinfunction "3_3") (pintype "passive"))
      (node (ref "J2") (pin "1") (pinfunction "Signal_1") (pintype "passive"))
      (node (ref "R39") (pin "1") (pinfunction "1_1") (pintype "passive"))
      (node (ref "TP3") (pin "1") (pinfunction "1_1") (pintype "passive"))
    )
    (net (code "66") (name "Net-(J3-Signal)") (class "Default")
      (node (ref "D3") (pin "3") (pinfunction "3_3") (pintype "passive"))
      (node (ref "J3") (pin "1") (pinfunction "Signal_1") (pintype "passive"))
      (node (ref "R43") (pin "2") (pinfunction "2_2") (pintype "passive"))
      (node (ref "TP5") (pin "1") (pinfunction "1_1") (pintype "passive"))
      (node (ref "U14") (pin "5") (pinfunction "TTLIN_5") (pintype "input"))
    )
    (net (code "67") (name "Net-(P11-Pad15)") (class "Default")
      (node (ref "P11") (pin "15") (pinfunction "15_15") (pintype "passive"))
      (node (ref "R40") (pin "2") (pinfunction "2_2") (pintype "passive"))
    )
    (net (code "68") (name "Net-(P11-Pad16)") (class "Default")
      (node (ref "P11") (pin "16") (pinfunction "16_16") (pintype "passive"))
      (node (ref "R41") (pin "1") (pinfunction "1_1") (pintype "passive"))
    )
    (net (code "69") (name "Net-(P12-Pad2)") (class "Default")
      (node (ref "P12") (pin "2") (pinfunction "2_2") (pintype "passive"))
      (node (ref "R42") (pin "1") (pinfunction "1_1") (pintype "passive"))
    )
    (net (code "70") (name "Net-(P12-Pad4)") (class "Default")
      (node (ref "P12") (pin "4") (pinfunction "4_4") (pintype "passive"))
      (node (ref "R44") (pin "1") (pinfunction "1_1") (pintype "passive"))
    )
    (net (code "71") (name "Net-(P12-Pad6)") (class "Default")
      (node (ref "P12") (pin "6") (pinfunction "6_6") (pintype "passive"))
      (node (ref "R45") (pin "1") (pinfunction "1_1") (pintype "passive"))
    )
    (net (code "72") (name "Net-(P12-Pad8)") (class "Default")
      (node (ref "P12") (pin "8") (pinfunction "8_8") (pintype "passive"))
      (node (ref "R46") (pin "1") (pinfunction "1_1") (pintype "passive"))
    )
    (net (code "73") (name "Net-(P12-Pad10)") (class "Default")
      (node (ref "P12") (pin "10") (pinfunction "10_10") (pintype "passive"))
      (node (ref "R47") (pin "1") (pinfunction "1_1") (pintype "passive"))
    )
    (net (code "74") (name "Net-(P12-Pad12)") (class "Default")
      (node (ref "P12") (pin "12") (pinfunction "12_12") (pintype "passive"))
      (node (ref "R48") (pin "1") (pinfunction "1_1") (pintype "passive"))
    )
    (net (code "75") (name "Net-(P12-Pad14)") (class "Default")
      (node (ref "P12") (pin "14") (pinfunction "14_14") (pintype "passive"))
      (node (ref "R49") (pin "1") (pinfunction "1_1") (pintype "passive"))
    )
    (net (code "76") (name "Net-(P12-Pad16)") (class "Default")
      (node (ref "P12") (pin "16") (pinfunction "16_16") (pintype "passive"))
      (node (ref "R50") (pin "1") (pinfunction "1_1") (pintype "passive"))
    )
    (net (code "77") (name "Net-(P12-Pad18)") (class "Default")
      (node (ref "P12") (pin "18") (pinfunction "18_18") (pintype "passive"))
      (node (ref "R51") (pin "1") (pinfunction "1_1") (pintype "passive"))
    )
    (net (code "78") (name "Net-(P12-Pad20)") (class "Default")
      (node (ref "P12") (pin "20") (pinfunction "20_20") (pintype "passive"))
      (node (ref "R52") (pin "1") (pinfunction "1_1") (pintype "passive"))
    )
    (net (code "79") (name "Net-(P12-Pad22)") (class "Default")
      (node (ref "P12") (pin "22") (pinfunction "22_22") (pintype "passive"))
      (node (ref "R53") (pin "1") (pinfunction "1_1") (pintype "passive"))
    )
    (net (code "80") (name "Net-(P12-Pad24)") (class "Default")
      (node (ref "P12") (pin "24") (pinfunction "24_24") (pintype "passive"))
      (node (ref "R54") (pin "1") (pinfunction "1_1") (pintype "passive"))
    )
    (net (code "81") (name "Net-(P12-Pad26)") (class "Default")
      (node (ref "P12") (pin "26") (pinfunction "26_26") (pintype "passive"))
      (node (ref "R55") (pin "1") (pinfunction "1_1") (pintype "passive"))
    )
    (net (code "82") (name "Net-(P12-Pad28)") (class "Default")
      (node (ref "P12") (pin "28") (pinfunction "28_28") (pintype "passive"))
      (node (ref "R56") (pin "1") (pinfunction "1_1") (pintype "passive"))
    )
    (net (code "83") (name "Net-(P12-Pad30)") (class "Default")
      (node (ref "P12") (pin "30") (pinfunction "30_30") (pintype "passive"))
      (node (ref "R57") (pin "1") (pinfunction "1_1") (pintype "passive"))
    )
    (net (code "84") (name "Net-(P15-Pad2)") (class "Default")
      (node (ref "P15") (pin "2") (pinfunction "2_2") (pintype "passive"))
      (node (ref "R58") (pin "1") (pinfunction "1_1") (pintype "passive"))
    )
    (net (code "85") (name "Net-(P15-Pad4)") (class "Default")
      (node (ref "P15") (pin "4") (pinfunction "4_4") (pintype "passive"))
      (node (ref "R59") (pin "1") (pinfunction "1_1") (pintype "passive"))
    )
    (net (code "86") (name "Net-(P15-Pad6)") (class "Default")
      (node (ref "P15") (pin "6") (pinfunction "6_6") (pintype "passive"))
      (node (ref "R60") (pin "1") (pinfunction "1_1") (pintype "passive"))
    )
    (net (code "87") (name "Net-(P15-Pad8)") (class "Default")
      (node (ref "P15") (pin "8") (pinfunction "8_8") (pintype "passive"))
      (node (ref "R61") (pin "1") (pinfunction "1_1") (pintype "passive"))
    )
    (net (code "88") (name "Net-(P15-Pad10)") (class "Default")
      (node (ref "P15") (pin "10") (pinfunction "10_10") (pintype "passive"))
      (node (ref "R62") (pin "1") (pinfunction "1_1") (pintype "passive"))
    )
    (net (code "89") (name "Net-(P15-Pad12)") (class "Default")
      (node (ref "P15") (pin "12") (pinfunction "12_12") (pintype "passive"))
      (node (ref "R63") (pin "1") (pinfunction "1_1") (pintype "passive"))
    )
    (net (code "90") (name "Net-(P15-Pad14)") (class "Default")
      (node (ref "P15") (pin "14") (pinfunction "14_14") (pintype "passive"))
      (node (ref "R64") (pin "1") (pinfunction "1_1") (pintype "passive"))
    )
    (net (code "91") (name "Net-(P15-Pad16)") (class "Default")
      (node (ref "P15") (pin "16") (pinfunction "16_16") (pintype "passive"))
      (node (ref "R65") (pin "1") (pinfunction "1_1") (pintype "passive"))
    )
    (net (code "92") (name "Net-(P15-Pad18)") (class "Default")
      (node (ref "P15") (pin "18") (pinfunction "18_18") (pintype "passive"))
      (node (ref "R66") (pin "1") (pinfunction "1_1") (pintype "passive"))
    )
    (net (code "93") (name "Net-(P15-Pad20)") (class "Default")
      (node (ref "P15") (pin "20") (pinfunction "20_20") (pintype "passive"))
      (node (ref "R67") (pin "1") (pinfunction "1_1") (pintype "passive"))
    )
    (net (code "94") (name "Net-(P15-Pad22)") (class "Default")
      (node (ref "P15") (pin "22") (pinfunction "22_22") (pintype "passive"))
      (node (ref "R68") (pin "1") (pinfunction "1_1") (pintype "passive"))
    )
    (net (code "95") (name "Net-(P15-Pad24)") (class "Default")
      (node (ref "P15") (pin "24") (pinfunction "24_24") (pintype "passive"))
      (node (ref "R69") (pin "1") (pinfunction "1_1") (pintype "passive"))
    )
    (net (code "96") (name "Net-(P15-Pad26)") (class "Default")
      (node (ref "P15") (pin "26") (pinfunction "26_26") (pintype "passive"))
      (node (ref "R70") (pin "1") (pinfunction "1_1") (pintype "passive"))
    )
    (net (code "97") (name "Net-(P15-Pad28)") (class "Default")
      (node (ref "P15") (pin "28") (pinfunction "28_28") (pintype "passive"))
      (node (ref "R71") (pin "1") (pinfunction "1_1") (pintype "passive"))
    )
    (net (code "98") (name "Net-(P15-Pad30)") (class "Default")
      (node (ref "P15") (pin "30") (pinfunction "30_30") (pintype "passive"))
      (node (ref "R72") (pin "1") (pinfunction "1_1") (pintype "passive"))
    )
    (net (code "99") (name "Net-(P16-Pad1)") (class "Default")
      (node (ref "P16") (pin "1") (pinfunction "1_1") (pintype "passive"))
      (node (ref "R73") (pin "2") (pinfunction "2_2") (pintype "passive"))
    )
    (net (code "100") (name "Net-(P16-Pad2)") (class "Default")
      (node (ref "P16") (pin "2") (pinfunction "2_2") (pintype "passive"))
      (node (ref "R74") (pin "1") (pinfunction "1_1") (pintype "passive"))
    )
    (net (code "101") (name "Net-(P16-Pad3)") (class "Default")
      (node (ref "P16") (pin "3") (pinfunction "3_3") (pintype "passive"))
      (node (ref "R75") (pin "2") (pinfunction "2_2") (pintype "passive"))
    )
    (net (code "102") (name "Net-(P16-Pad4)") (class "Default")
      (node (ref "P16") (pin "4") (pinfunction "4_4") (pintype "passive"))
      (node (ref "R76") (pin "1") (pinfunction "1_1") (pintype "passive"))
    )
    (net (code "103") (name "Net-(P17-Pad1)") (class "Default")
      (node (ref "P17") (pin "1") (pinfunction "1_1") (pintype "passive"))
      (node (ref "R77") (pin "2") (pinfunction "2_2") (pintype "passive"))
    )
    (net (code "104") (name "Net-(P17-Pad2)") (class "Default")
      (node (ref "P17") (pin "2") (pinfunction "2_2") (pintype "passive"))
      (node (ref "R78") (pin "1") (pinfunction "1_1") (pintype "passive"))
    )
    (net (code "105") (name "Net-(P17-Pad3)") (class "Default")
      (node (ref "P17") (pin "3") (pinfunction "3_3") (pintype "passive"))
      (node (ref "R79") (pin "2") (pinfunction "2_2") (pintype "passive"))
    )
    (net (code "106") (name "Net-(P17-Pad4)") (class "Default")
      (node (ref "P17") (pin "4") (pinfunction "4_4") (pintype "passive"))
      (node (ref "R80") (pin "1") (pinfunction "1_1") (pintype "passive"))
    )
    (net (code "107") (name "Net-(U13-TTLOUT)") (class "Default")
      (node (ref "R39") (pin "2") (pinfunction "2_2") (pintype "passive"))
      (node (ref "U13") (pin "5") (pinfunction "TTLOUT_5") (pintype "output"))
    )
    (net (code "108") (name "unconnected-(P13-Pad7)") (class "Default")
      (node (ref "P13") (pin "7") (pinfunction "7_7") (pintype "passive"))
    )
    (net (code "109") (name "unconnected-(P13-Pad8)") (class "Default")
      (node (ref "P13") (pin "8") (pinfunction "8_8") (pintype "passive"))
    )
    (net (code "110") (name "unconnected-(P14-Pad7)") (class "Default")
      (node (ref "P14") (pin "7") (pinfunction "7_7") (pintype "passive"))
    )
    (net (code "111") (name "unconnected-(P14-Pad8)") (class "Default")
      (node (ref "P14") (pin "8") (pinfunction "8_8") (pintype "passive"))
    )
  )
)
